# osbo_v10.net
KiCad netlist of a schematic drawn in EAGLE
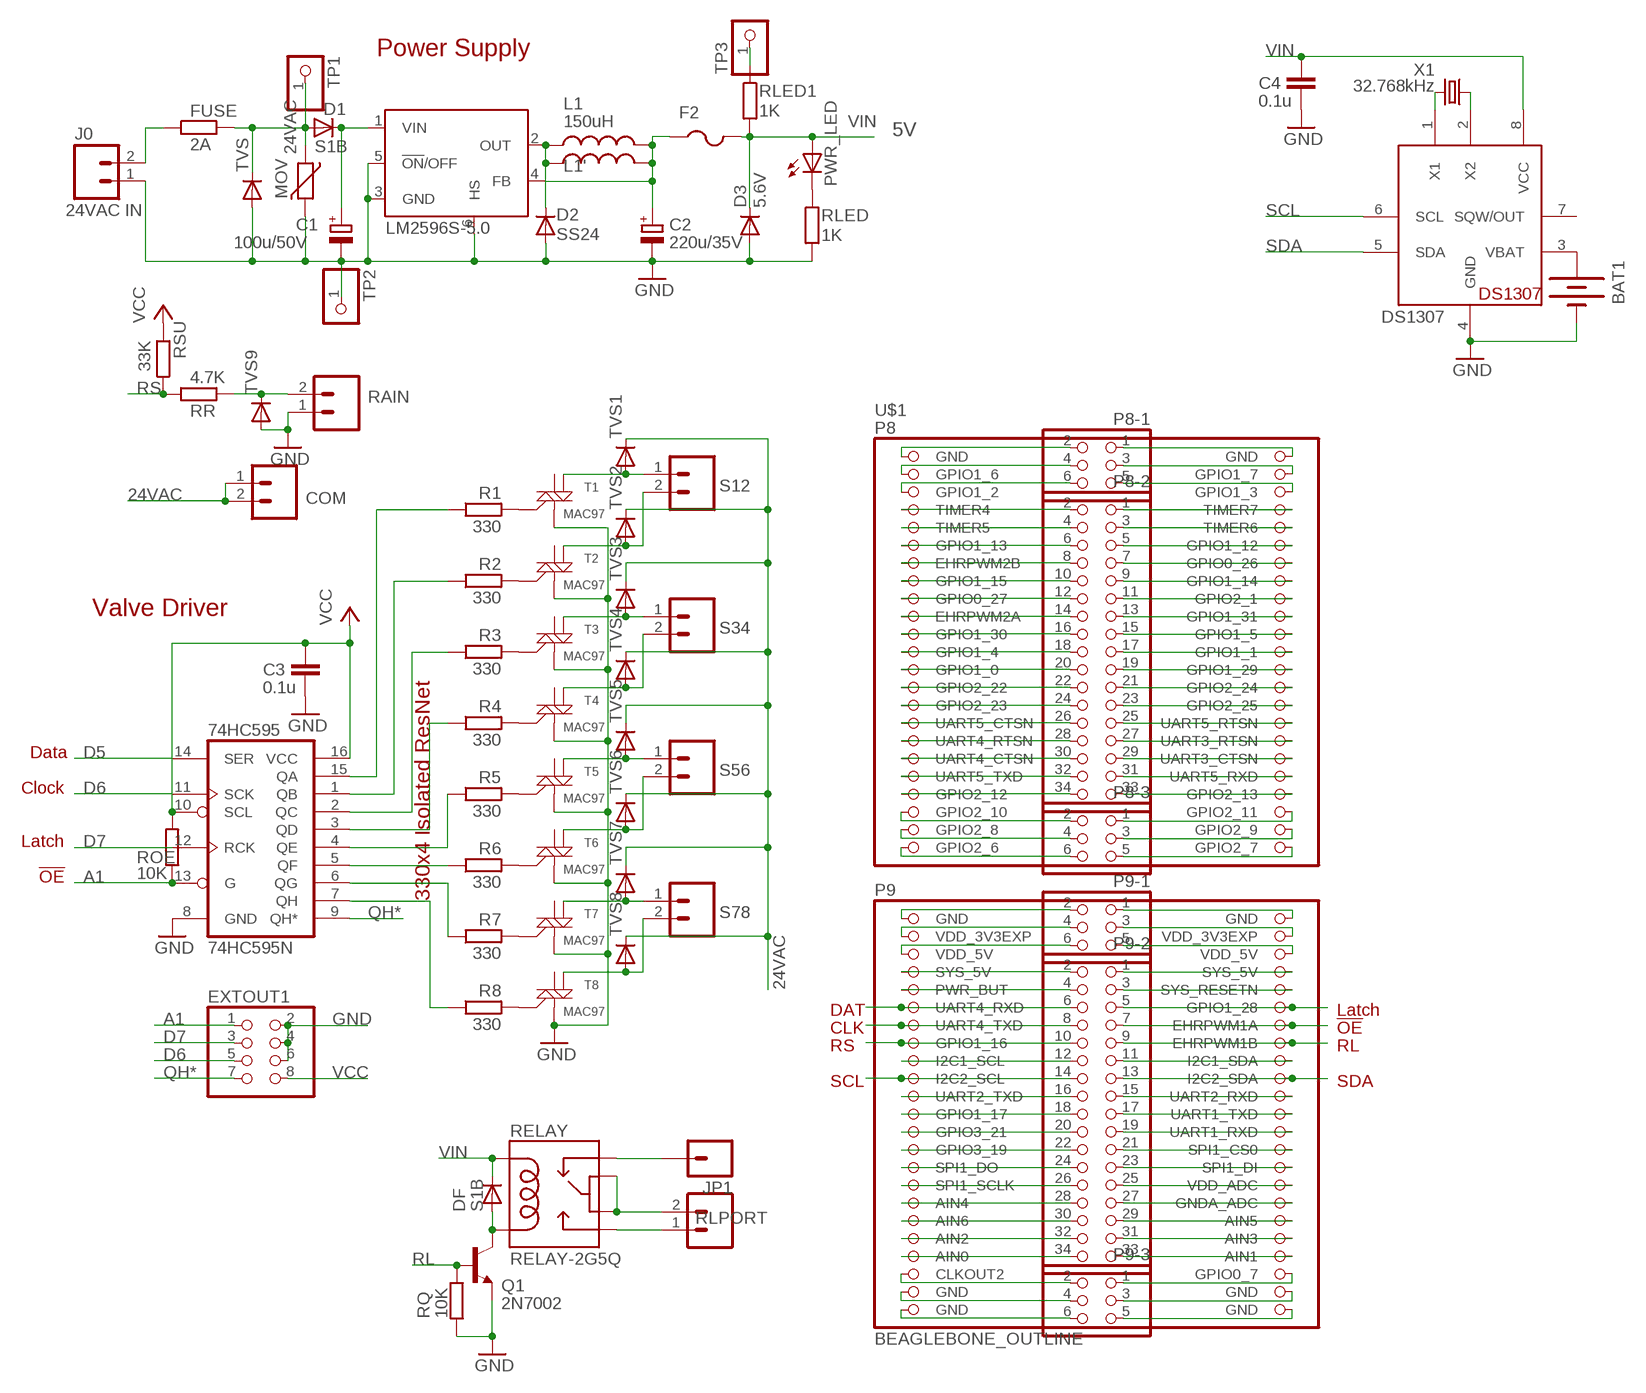
[diagram p0: schematic, sheet 1]

(export (version "E")
  (design (tool "Eeschema 10.0.6"))
  (components
    (comp (ref "74HC595")
      (value "74HC595N")
      (footprint "eagle-import:SO16")
      (libsource (lib "eagle-import") (part "74595DLS"))
    )
    (comp (ref "BAT1")
      (value "BATTERYBATTERY_12MM_SMT")
      (footprint "eagle-import:BATTCON_12MM_SMT")
      (libsource (lib "eagle-import") (part "BATTERYBATTERY_12MM_SMT"))
    )
    (comp (ref "C1")
      (value "100u/50V")
      (footprint "eagle-import:PANASONIC_E")
      (libsource (lib "eagle-import") (part "CPOL-EUE"))
    )
    (comp (ref "C2")
      (value "220u/35V")
      (footprint "eagle-import:PANASONIC_E")
      (libsource (lib "eagle-import") (part "CPOL-EUE"))
    )
    (comp (ref "C3")
      (value "0.1u")
      (footprint "eagle-import:C0805")
      (libsource (lib "eagle-import") (part "C-EUC0805"))
    )
    (comp (ref "C4")
      (value "0.1u")
      (footprint "eagle-import:C0805")
      (libsource (lib "eagle-import") (part "C-EUC0805"))
    )
    (comp (ref "COM")
      (value "M025MM-X")
      (footprint "eagle-import:SCREWTERMINAL-5MM-2-X")
      (libsource (lib "eagle-import") (part "M025MM-X"))
    )
    (comp (ref "D1")
      (value "S1B")
      (footprint "eagle-import:DO-214AC")
      (libsource (lib "eagle-import") (part "DIODE-DO-214AC"))
    )
    (comp (ref "D2")
      (value "SS24")
      (footprint "eagle-import:SMB")
      (libsource (lib "eagle-import") (part "DIODE-SMB"))
    )
    (comp (ref "D3")
      (value "5.6V")
      (footprint "eagle-import:MINIMELF")
      (libsource (lib "eagle-import") (part "DIODE-MINIMELF"))
    )
    (comp (ref "DF")
      (value "S1B")
      (footprint "eagle-import:DO-214AC")
      (libsource (lib "eagle-import") (part "DIODE-DO-214AC"))
    )
    (comp (ref "DS1307")
      (value "DS1307")
      (footprint "eagle-import:SO08")
      (libsource (lib "eagle-import") (part "DS1307SOIC"))
    )
    (comp (ref "EXTOUT1")
      (value "PINHD-2X4/90")
      (footprint "eagle-import:2X04_90")
      (libsource (lib "eagle-import") (part "PINHD-2X4/90"))
    )
    (comp (ref "F2")
      (value "PTCFUSE-1812")
      (footprint "eagle-import:1812")
      (libsource (lib "eagle-import") (part "PTCFUSE-1812"))
    )
    (comp (ref "FUSE")
      (value "2A")
      (footprint "eagle-import:0411_15")
      (libsource (lib "eagle-import") (part "R-EU_0411/15"))
    )
    (comp (ref "IC1")
      (value "LM2596S-5.0")
      (footprint "eagle-import:TO263-5")
      (fields (field (name "MF") "NATIONAL SEMICONDUCTOR") (field (name "MPN") "LM2596S-ADJ/NOPB"))
      (libsource (lib "eagle-import") (part "LM2596S"))
    )
    (comp (ref "J0")
      (value "24VAC IN")
      (footprint "eagle-import:SCREWTERMINAL-4MM-2-X")
      (libsource (lib "eagle-import") (part "M024MM-X"))
    )
    (comp (ref "JP1")
      (value "M01PTH")
      (footprint "eagle-import:1X01")
      (libsource (lib "eagle-import") (part "M01PTH"))
    )
    (comp (ref "L1")
      (value "150uH")
      (footprint "eagle-import:CDRH125")
      (libsource (lib "eagle-import") (part "INDUCTORPWR"))
    )
    (comp (ref "L1'")
      (value "150uH")
      (footprint "eagle-import:0207_7")
      (libsource (lib "eagle-import") (part "L-US0207/7"))
    )
    (comp (ref "MOV")
      (value "VARISTOR-5")
      (footprint "eagle-import:R-5")
      (libsource (lib "eagle-import") (part "VARISTOR-5"))
    )
    (comp (ref "P8-1")
      (value "PINHD-2X3")
      (footprint "eagle-import:2X03")
      (libsource (lib "eagle-import") (part "PINHD-2X3"))
    )
    (comp (ref "P8-2")
      (value "PINHD-2X17")
      (footprint "eagle-import:2X17")
      (libsource (lib "eagle-import") (part "PINHD-2X17"))
    )
    (comp (ref "P8-3")
      (value "PINHD-2X3")
      (footprint "eagle-import:2X03")
      (libsource (lib "eagle-import") (part "PINHD-2X3"))
    )
    (comp (ref "P9-1")
      (value "PINHD-2X3")
      (footprint "eagle-import:2X03")
      (libsource (lib "eagle-import") (part "PINHD-2X3"))
    )
    (comp (ref "P9-2")
      (value "PINHD-2X17")
      (footprint "eagle-import:2X17")
      (libsource (lib "eagle-import") (part "PINHD-2X17"))
    )
    (comp (ref "P9-3")
      (value "PINHD-2X3")
      (footprint "eagle-import:2X03")
      (libsource (lib "eagle-import") (part "PINHD-2X3"))
    )
    (comp (ref "PWR_LED")
      (value "LEDCHIPLED_0805")
      (footprint "eagle-import:CHIPLED_0805")
      (libsource (lib "eagle-import") (part "LEDCHIPLED_0805"))
    )
    (comp (ref "Q1")
      (value "2N7002")
      (footprint "eagle-import:SOT23-3")
      (libsource (lib "eagle-import") (part "TRANSISTOR_NPNSOT23-3"))
    )
    (comp (ref "R1")
      (value "330")
      (footprint "eagle-import:R0805")
      (libsource (lib "eagle-import") (part "R-EU_R0805"))
    )
    (comp (ref "R2")
      (value "330")
      (footprint "eagle-import:R0805")
      (libsource (lib "eagle-import") (part "R-EU_R0805"))
    )
    (comp (ref "R3")
      (value "330")
      (footprint "eagle-import:R0805")
      (libsource (lib "eagle-import") (part "R-EU_R0805"))
    )
    (comp (ref "R4")
      (value "330")
      (footprint "eagle-import:R0805")
      (libsource (lib "eagle-import") (part "R-EU_R0805"))
    )
    (comp (ref "R5")
      (value "330")
      (footprint "eagle-import:R0805")
      (libsource (lib "eagle-import") (part "R-EU_R0805"))
    )
    (comp (ref "R6")
      (value "330")
      (footprint "eagle-import:R0805")
      (libsource (lib "eagle-import") (part "R-EU_R0805"))
    )
    (comp (ref "R7")
      (value "330")
      (footprint "eagle-import:R0805")
      (libsource (lib "eagle-import") (part "R-EU_R0805"))
    )
    (comp (ref "R8")
      (value "330")
      (footprint "eagle-import:R0805")
      (libsource (lib "eagle-import") (part "R-EU_R0805"))
    )
    (comp (ref "RAIN")
      (value "M025MM-X")
      (footprint "eagle-import:SCREWTERMINAL-5MM-2-X")
      (libsource (lib "eagle-import") (part "M025MM-X"))
    )
    (comp (ref "RELAY")
      (value "RELAY-2G5Q")
      (footprint "eagle-import:RELAY-G5V")
      (libsource (lib "eagle-import") (part "RELAY-2G5Q"))
    )
    (comp (ref "RLED")
      (value "1K")
      (footprint "eagle-import:R0805")
      (libsource (lib "eagle-import") (part "R-EU_R0805"))
    )
    (comp (ref "RLED1")
      (value "1K")
      (footprint "eagle-import:R0805")
      (libsource (lib "eagle-import") (part "R-EU_R0805"))
    )
    (comp (ref "RLPORT")
      (value "M025MM")
      (footprint "eagle-import:SCREWTERMINAL-5MM-2")
      (libsource (lib "eagle-import") (part "M025MM"))
    )
    (comp (ref "ROE")
      (value "10K")
      (footprint "eagle-import:R0805")
      (libsource (lib "eagle-import") (part "R-EU_R0805"))
    )
    (comp (ref "RQ")
      (value "10K")
      (footprint "eagle-import:R0805")
      (libsource (lib "eagle-import") (part "R-EU_R0805"))
    )
    (comp (ref "RR")
      (value "4.7K")
      (footprint "eagle-import:R0805")
      (libsource (lib "eagle-import") (part "R-EU_R0805"))
    )
    (comp (ref "RSU")
      (value "33K")
      (footprint "eagle-import:R0805")
      (libsource (lib "eagle-import") (part "R-EU_R0805"))
    )
    (comp (ref "S12")
      (value "M025MM-X")
      (footprint "eagle-import:SCREWTERMINAL-5MM-2-X")
      (libsource (lib "eagle-import") (part "M025MM-X"))
    )
    (comp (ref "S34")
      (value "M025MM-X")
      (footprint "eagle-import:SCREWTERMINAL-5MM-2-X")
      (libsource (lib "eagle-import") (part "M025MM-X"))
    )
    (comp (ref "S56")
      (value "M025MM-X")
      (footprint "eagle-import:SCREWTERMINAL-5MM-2-X")
      (libsource (lib "eagle-import") (part "M025MM-X"))
    )
    (comp (ref "S78")
      (value "M025MM-X")
      (footprint "eagle-import:SCREWTERMINAL-5MM-2-X")
      (libsource (lib "eagle-import") (part "M025MM-X"))
    )
    (comp (ref "T1")
      (value "MAC97")
      (footprint "eagle-import:SOT223")
      (libsource (lib "eagle-import") (part "MAC97SOT223"))
    )
    (comp (ref "T2")
      (value "MAC97")
      (footprint "eagle-import:SOT223")
      (libsource (lib "eagle-import") (part "MAC97SOT223"))
    )
    (comp (ref "T3")
      (value "MAC97")
      (footprint "eagle-import:SOT223")
      (libsource (lib "eagle-import") (part "MAC97SOT223"))
    )
    (comp (ref "T4")
      (value "MAC97")
      (footprint "eagle-import:SOT223")
      (libsource (lib "eagle-import") (part "MAC97SOT223"))
    )
    (comp (ref "T5")
      (value "MAC97")
      (footprint "eagle-import:SOT223")
      (libsource (lib "eagle-import") (part "MAC97SOT223"))
    )
    (comp (ref "T6")
      (value "MAC97")
      (footprint "eagle-import:SOT223")
      (libsource (lib "eagle-import") (part "MAC97SOT223"))
    )
    (comp (ref "T7")
      (value "MAC97")
      (footprint "eagle-import:SOT223")
      (libsource (lib "eagle-import") (part "MAC97SOT223"))
    )
    (comp (ref "T8")
      (value "MAC97")
      (footprint "eagle-import:SOT223")
      (libsource (lib "eagle-import") (part "MAC97SOT223"))
    )
    (comp (ref "TP1")
      (value "PINHD-1X1CB")
      (footprint "eagle-import:1X01-CLEANBIG")
      (libsource (lib "eagle-import") (part "PINHD-1X1CB"))
    )
    (comp (ref "TP2")
      (value "PINHD-1X1CB")
      (footprint "eagle-import:1X01-CLEANBIG")
      (libsource (lib "eagle-import") (part "PINHD-1X1CB"))
    )
    (comp (ref "TP3")
      (value "PINHD-1X1CB")
      (footprint "eagle-import:1X01-CLEANBIG")
      (libsource (lib "eagle-import") (part "PINHD-1X1CB"))
    )
    (comp (ref "TVS")
      (value "DIODE-SMB")
      (footprint "eagle-import:SMB")
      (libsource (lib "eagle-import") (part "DIODE-SMB"))
    )
    (comp (ref "TVS1")
      (value "DIODE-SMB")
      (footprint "eagle-import:SMB")
      (libsource (lib "eagle-import") (part "DIODE-SMB"))
    )
    (comp (ref "TVS2")
      (value "DIODE-SMB")
      (footprint "eagle-import:SMB")
      (libsource (lib "eagle-import") (part "DIODE-SMB"))
    )
    (comp (ref "TVS3")
      (value "DIODE-SMB")
      (footprint "eagle-import:SMB")
      (libsource (lib "eagle-import") (part "DIODE-SMB"))
    )
    (comp (ref "TVS4")
      (value "DIODE-SMB")
      (footprint "eagle-import:SMB")
      (libsource (lib "eagle-import") (part "DIODE-SMB"))
    )
    (comp (ref "TVS5")
      (value "DIODE-SMB")
      (footprint "eagle-import:SMB")
      (libsource (lib "eagle-import") (part "DIODE-SMB"))
    )
    (comp (ref "TVS6")
      (value "DIODE-SMB")
      (footprint "eagle-import:SMB")
      (libsource (lib "eagle-import") (part "DIODE-SMB"))
    )
    (comp (ref "TVS7")
      (value "DIODE-SMB")
      (footprint "eagle-import:SMB")
      (libsource (lib "eagle-import") (part "DIODE-SMB"))
    )
    (comp (ref "TVS8")
      (value "DIODE-SMB")
      (footprint "eagle-import:SMB")
      (libsource (lib "eagle-import") (part "DIODE-SMB"))
    )
    (comp (ref "TVS9")
      (value "DIODE-SMB")
      (footprint "eagle-import:SMB")
      (libsource (lib "eagle-import") (part "DIODE-SMB"))
    )
    (comp (ref "U$1")
      (value "BEAGLEBONE_OUTLINE")
      (footprint "eagle-import:BEAGLEBONE_SHIELD")
      (libsource (lib "eagle-import") (part "BEAGLEBONE_OUTLINE"))
    )
    (comp (ref "X1")
      (value "32.768kHz")
      (footprint "eagle-import:MM20SS")
      (libsource (lib "eagle-import") (part "CRYSTALMM20SS"))
    )
  )
  (nets
    (net (code "1") (name "/24VAC") (class "Default")
      (node (ref "COM") (pin "1") (pinfunction "1_1") (pintype "passive"))
      (node (ref "COM") (pin "2") (pinfunction "2_2") (pintype "passive"))
      (node (ref "D1") (pin "A") (pinfunction "A_A") (pintype "passive"))
      (node (ref "FUSE") (pin "2") (pinfunction "2_2") (pintype "passive"))
      (node (ref "MOV") (pin "1") (pinfunction "1_1") (pintype "passive"))
      (node (ref "TP1") (pin "1") (pinfunction "1_1") (pintype "passive"))
      (node (ref "TVS") (pin "C") (pinfunction "C_C") (pintype "passive"))
      (node (ref "TVS1") (pin "C") (pinfunction "C_C") (pintype "passive"))
      (node (ref "TVS2") (pin "C") (pinfunction "C_C") (pintype "passive"))
      (node (ref "TVS3") (pin "C") (pinfunction "C_C") (pintype "passive"))
      (node (ref "TVS4") (pin "C") (pinfunction "C_C") (pintype "passive"))
      (node (ref "TVS5") (pin "C") (pinfunction "C_C") (pintype "passive"))
      (node (ref "TVS6") (pin "C") (pinfunction "C_C") (pintype "passive"))
      (node (ref "TVS7") (pin "C") (pinfunction "C_C") (pintype "passive"))
      (node (ref "TVS8") (pin "C") (pinfunction "C_C") (pintype "passive"))
    )
    (net (code "2") (name "/A1") (class "Default")
      (node (ref "74HC595") (pin "13") (pinfunction "G_13") (pintype "input"))
      (node (ref "EXTOUT1") (pin "1") (pinfunction "1_1") (pintype "passive"))
      (node (ref "P9-2") (pin "7") (pinfunction "7_7") (pintype "passive"))
      (node (ref "ROE") (pin "1") (pinfunction "1_1") (pintype "passive"))
      (node (ref "U$1") (pin "60") (pinfunction "EHRPWM1A_60") (pintype "passive"))
    )
    (net (code "3") (name "/D5") (class "Default")
      (node (ref "74HC595") (pin "14") (pinfunction "SER_14") (pintype "input"))
      (node (ref "P9-2") (pin "6") (pinfunction "6_6") (pintype "passive"))
      (node (ref "U$1") (pin "57") (pinfunction "UART4_RXD_57") (pintype "passive"))
    )
    (net (code "4") (name "/D6") (class "Default")
      (node (ref "74HC595") (pin "11") (pinfunction "SCK_11") (pintype "input"))
      (node (ref "EXTOUT1") (pin "5") (pinfunction "5_5") (pintype "passive"))
      (node (ref "P9-2") (pin "8") (pinfunction "8_8") (pintype "passive"))
      (node (ref "U$1") (pin "59") (pinfunction "UART4_TXD_59") (pintype "passive"))
    )
    (net (code "5") (name "/D7") (class "Default")
      (node (ref "74HC595") (pin "12") (pinfunction "RCK_12") (pintype "input"))
      (node (ref "EXTOUT1") (pin "3") (pinfunction "3_3") (pintype "passive"))
      (node (ref "P9-2") (pin "5") (pinfunction "5_5") (pintype "passive"))
      (node (ref "U$1") (pin "58") (pinfunction "GPIO1_28_58") (pintype "passive"))
    )
    (net (code "6") (name "/QH*") (class "Default")
      (node (ref "74HC595") (pin "9") (pinfunction "QH*_9") (pintype "tri_state"))
      (node (ref "EXTOUT1") (pin "7") (pinfunction "7_7") (pintype "passive"))
    )
    (net (code "7") (name "/RL") (class "Default")
      (node (ref "P9-2") (pin "9") (pinfunction "9_9") (pintype "passive"))
      (node (ref "Q1") (pin "1") (pinfunction "B_1") (pintype "passive"))
      (node (ref "RQ") (pin "1") (pinfunction "1_1") (pintype "passive"))
      (node (ref "U$1") (pin "62") (pinfunction "EHRPWM1B_62") (pintype "passive"))
    )
    (net (code "8") (name "/RS") (class "Default")
      (node (ref "P9-2") (pin "10") (pinfunction "10_10") (pintype "passive"))
      (node (ref "RR") (pin "2") (pinfunction "2_2") (pintype "passive"))
      (node (ref "RSU") (pin "1") (pinfunction "1_1") (pintype "passive"))
      (node (ref "U$1") (pin "61") (pinfunction "GPIO1_16_61") (pintype "passive"))
    )
    (net (code "9") (name "/SCL") (class "Default")
      (node (ref "DS1307") (pin "6") (pinfunction "SCL_6") (pintype "bidirectional"))
      (node (ref "P9-2") (pin "14") (pinfunction "14_14") (pintype "passive"))
      (node (ref "U$1") (pin "65") (pinfunction "I2C2_SCL_65") (pintype "passive"))
    )
    (net (code "10") (name "/SDA") (class "Default")
      (node (ref "DS1307") (pin "5") (pinfunction "SDA_5") (pintype "bidirectional"))
      (node (ref "P9-2") (pin "13") (pinfunction "13_13") (pintype "passive"))
      (node (ref "U$1") (pin "66") (pinfunction "I2C2_SDA_66") (pintype "passive"))
    )
    (net (code "11") (name "/SYS_5V") (class "Default")
      (node (ref "P9-2") (pin "1") (pinfunction "1_1") (pintype "passive"))
      (node (ref "P9-2") (pin "2") (pinfunction "2_2") (pintype "passive"))
      (node (ref "U$1") (pin "53") (pinfunction "SYS_5V_53") (pintype "power_in"))
      (node (ref "U$1") (pin "54") (pinfunction "SYS_5V_54") (pintype "passive"))
    )
    (net (code "12") (name "/VIN") (class "Default")
      (node (ref "C4") (pin "1") (pinfunction "1_1") (pintype "passive"))
      (node (ref "D3") (pin "C") (pinfunction "C_C") (pintype "passive"))
      (node (ref "DF") (pin "C") (pinfunction "C_C") (pintype "passive"))
      (node (ref "DS1307") (pin "8") (pinfunction "VCC_8") (pintype "power_in"))
      (node (ref "F2") (pin "2") (pinfunction "2_2") (pintype "passive"))
      (node (ref "P9-1") (pin "5") (pinfunction "5_5") (pintype "passive"))
      (node (ref "P9-1") (pin "6") (pinfunction "6_6") (pintype "passive"))
      (node (ref "PWR_LED") (pin "A") (pinfunction "A_A") (pintype "passive"))
      (node (ref "RELAY") (pin "2") (pinfunction "2_2") (pintype "bidirectional"))
      (node (ref "RLED1") (pin "2") (pinfunction "2_2") (pintype "passive"))
      (node (ref "U$1") (pin "51") (pinfunction "VDD_5V_51") (pintype "power_in"))
      (node (ref "U$1") (pin "52") (pinfunction "VDD_5V_52") (pintype "power_in"))
    )
    (net (code "13") (name "GND") (class "Default")
      (node (ref "74HC595") (pin "8") (pinfunction "GND_8") (pintype "power_in"))
      (node (ref "BAT1") (pin "P$1") (pinfunction "-_P$1") (pintype "power_in"))
      (node (ref "C1") (pin "-") (pinfunction "-_-") (pintype "passive"))
      (node (ref "C2") (pin "-") (pinfunction "-_-") (pintype "passive"))
      (node (ref "C3") (pin "2") (pinfunction "2_2") (pintype "passive"))
      (node (ref "C4") (pin "2") (pinfunction "2_2") (pintype "passive"))
      (node (ref "D2") (pin "A") (pinfunction "A_A") (pintype "passive"))
      (node (ref "D3") (pin "A") (pinfunction "A_A") (pintype "passive"))
      (node (ref "DS1307") (pin "4") (pinfunction "GND_4") (pintype "power_in"))
      (node (ref "EXTOUT1") (pin "2") (pinfunction "2_2") (pintype "passive"))
      (node (ref "EXTOUT1") (pin "4") (pinfunction "4_4") (pintype "passive"))
      (node (ref "EXTOUT1") (pin "6") (pinfunction "6_6") (pintype "passive"))
      (node (ref "IC1") (pin "3") (pinfunction "GND_3") (pintype "power_in"))
      (node (ref "IC1") (pin "5") (pinfunction "~{ON}/OFF_5") (pintype "input"))
      (node (ref "IC1") (pin "6") (pinfunction "HS_6") (pintype "power_in"))
      (node (ref "J0") (pin "1") (pinfunction "1_1") (pintype "passive"))
      (node (ref "MOV") (pin "2") (pinfunction "2_2") (pintype "passive"))
      (node (ref "P9-1") (pin "1") (pinfunction "1_1") (pintype "passive"))
      (node (ref "P9-1") (pin "2") (pinfunction "2_2") (pintype "passive"))
      (node (ref "Q1") (pin "2") (pinfunction "E_2") (pintype "passive"))
      (node (ref "RAIN") (pin "1") (pinfunction "1_1") (pintype "passive"))
      (node (ref "RLED") (pin "2") (pinfunction "2_2") (pintype "passive"))
      (node (ref "RQ") (pin "2") (pinfunction "2_2") (pintype "passive"))
      (node (ref "T1") (pin "1") (pinfunction "M1_1") (pintype "bidirectional"))
      (node (ref "T2") (pin "1") (pinfunction "M1_1") (pintype "bidirectional"))
      (node (ref "T3") (pin "1") (pinfunction "M1_1") (pintype "bidirectional"))
      (node (ref "T4") (pin "1") (pinfunction "M1_1") (pintype "bidirectional"))
      (node (ref "T5") (pin "1") (pinfunction "M1_1") (pintype "bidirectional"))
      (node (ref "T6") (pin "1") (pinfunction "M1_1") (pintype "bidirectional"))
      (node (ref "T7") (pin "1") (pinfunction "M1_1") (pintype "bidirectional"))
      (node (ref "T8") (pin "1") (pinfunction "M1_1") (pintype "bidirectional"))
      (node (ref "TP2") (pin "1") (pinfunction "1_1") (pintype "passive"))
      (node (ref "TVS") (pin "A") (pinfunction "A_A") (pintype "passive"))
      (node (ref "TVS9") (pin "A") (pinfunction "A_A") (pintype "passive"))
      (node (ref "U$1") (pin "47") (pinfunction "GND_47") (pintype "power_in"))
      (node (ref "U$1") (pin "48") (pinfunction "GND_48") (pintype "power_in"))
    )
    (net (code "14") (name "Net-(74HC595-QA)") (class "Default")
      (node (ref "74HC595") (pin "15") (pinfunction "QA_15") (pintype "tri_state"))
      (node (ref "R1") (pin "1") (pinfunction "1_1") (pintype "passive"))
    )
    (net (code "15") (name "Net-(74HC595-QB)") (class "Default")
      (node (ref "74HC595") (pin "1") (pinfunction "QB_1") (pintype "tri_state"))
      (node (ref "R2") (pin "1") (pinfunction "1_1") (pintype "passive"))
    )
    (net (code "16") (name "Net-(74HC595-QC)") (class "Default")
      (node (ref "74HC595") (pin "2") (pinfunction "QC_2") (pintype "tri_state"))
      (node (ref "R3") (pin "1") (pinfunction "1_1") (pintype "passive"))
    )
    (net (code "17") (name "Net-(74HC595-QD)") (class "Default")
      (node (ref "74HC595") (pin "3") (pinfunction "QD_3") (pintype "tri_state"))
      (node (ref "R4") (pin "1") (pinfunction "1_1") (pintype "passive"))
    )
    (net (code "18") (name "Net-(74HC595-QE)") (class "Default")
      (node (ref "74HC595") (pin "4") (pinfunction "QE_4") (pintype "tri_state"))
      (node (ref "R5") (pin "1") (pinfunction "1_1") (pintype "passive"))
    )
    (net (code "19") (name "Net-(74HC595-QF)") (class "Default")
      (node (ref "74HC595") (pin "5") (pinfunction "QF_5") (pintype "tri_state"))
      (node (ref "R6") (pin "1") (pinfunction "1_1") (pintype "passive"))
    )
    (net (code "20") (name "Net-(74HC595-QG)") (class "Default")
      (node (ref "74HC595") (pin "6") (pinfunction "QG_6") (pintype "tri_state"))
      (node (ref "R7") (pin "1") (pinfunction "1_1") (pintype "passive"))
    )
    (net (code "21") (name "Net-(74HC595-QH)") (class "Default")
      (node (ref "74HC595") (pin "7") (pinfunction "QH_7") (pintype "tri_state"))
      (node (ref "R8") (pin "1") (pinfunction "1_1") (pintype "passive"))
    )
    (net (code "22") (name "Net-(BAT1-+)") (class "Default")
      (node (ref "BAT1") (pin "P$2") (pinfunction "+_P$2") (pintype "power_in"))
      (node (ref "DS1307") (pin "3") (pinfunction "VBAT_3") (pintype "power_in"))
    )
    (net (code "23") (name "Net-(DS1307-X1)") (class "Default")
      (node (ref "DS1307") (pin "1") (pinfunction "X1_1") (pintype "passive"))
      (node (ref "X1") (pin "1") (pinfunction "1_1") (pintype "passive"))
    )
    (net (code "24") (name "Net-(DS1307-X2)") (class "Default")
      (node (ref "DS1307") (pin "2") (pinfunction "X2_2") (pintype "passive"))
      (node (ref "X1") (pin "4") (pinfunction "2_4") (pintype "passive"))
    )
    (net (code "25") (name "Net-(FUSE-Pad1)") (class "Default")
      (node (ref "FUSE") (pin "1") (pinfunction "1_1") (pintype "passive"))
      (node (ref "J0") (pin "2") (pinfunction "2_2") (pintype "passive"))
    )
    (net (code "26") (name "Net-(IC1-FB)") (class "Default")
      (node (ref "C2") (pin "+") (pinfunction "+_+") (pintype "passive"))
      (node (ref "F2") (pin "1") (pinfunction "1_1") (pintype "passive"))
      (node (ref "IC1") (pin "4") (pinfunction "FB_4") (pintype "input"))
      (node (ref "L1") (pin "2") (pinfunction "2_2") (pintype "passive"))
      (node (ref "L1'") (pin "2") (pinfunction "2_2") (pintype "passive"))
    )
    (net (code "27") (name "Net-(IC1-OUT)") (class "Default")
      (node (ref "D2") (pin "C") (pinfunction "C_C") (pintype "passive"))
      (node (ref "IC1") (pin "2") (pinfunction "OUT_2") (pintype "output"))
      (node (ref "L1") (pin "1") (pinfunction "1_1") (pintype "passive"))
      (node (ref "L1'") (pin "1") (pinfunction "1_1") (pintype "passive"))
    )
    (net (code "28") (name "Net-(IC1-VIN)") (class "Default")
      (node (ref "C1") (pin "+") (pinfunction "+_+") (pintype "passive"))
      (node (ref "D1") (pin "C") (pinfunction "C_C") (pintype "passive"))
      (node (ref "IC1") (pin "1") (pinfunction "VIN_1") (pintype "input"))
    )
    (net (code "29") (name "Net-(JP1-Pad1)") (class "Default")
      (node (ref "JP1") (pin "1") (pinfunction "1_1") (pintype "passive"))
      (node (ref "RELAY") (pin "1") (pinfunction "1_1") (pintype "bidirectional"))
    )
    (net (code "30") (name "Net-(P8-1-Pad1)") (class "Default")
      (node (ref "P8-1") (pin "1") (pinfunction "1_1") (pintype "passive"))
      (node (ref "U$1") (pin "2") (pinfunction "GND_2") (pintype "power_in"))
    )
    (net (code "31") (name "Net-(P8-1-Pad2)") (class "Default")
      (node (ref "P8-1") (pin "2") (pinfunction "2_2") (pintype "passive"))
      (node (ref "U$1") (pin "1") (pinfunction "GND_1") (pintype "power_in"))
    )
    (net (code "32") (name "Net-(P9-3-Pad3)") (class "Default")
      (node (ref "P9-3") (pin "3") (pinfunction "3_3") (pintype "passive"))
      (node (ref "U$1") (pin "90") (pinfunction "GND_90") (pintype "power_in"))
    )
    (net (code "33") (name "Net-(P9-3-Pad4)") (class "Default")
      (node (ref "P9-3") (pin "4") (pinfunction "4_4") (pintype "passive"))
      (node (ref "U$1") (pin "89") (pinfunction "GND_89") (pintype "power_in"))
    )
    (net (code "34") (name "Net-(P9-3-Pad5)") (class "Default")
      (node (ref "P9-3") (pin "5") (pinfunction "5_5") (pintype "passive"))
      (node (ref "U$1") (pin "92") (pinfunction "GND_92") (pintype "power_in"))
    )
    (net (code "35") (name "Net-(P9-3-Pad6)") (class "Default")
      (node (ref "P9-3") (pin "6") (pinfunction "6_6") (pintype "passive"))
      (node (ref "U$1") (pin "91") (pinfunction "GND_91") (pintype "power_in"))
    )
    (net (code "36") (name "Net-(PWR_LED-PadC)") (class "Default")
      (node (ref "PWR_LED") (pin "C") (pinfunction "C_C") (pintype "passive"))
      (node (ref "RLED") (pin "1") (pinfunction "1_1") (pintype "passive"))
    )
    (net (code "37") (name "Net-(Q1-C)") (class "Default")
      (node (ref "DF") (pin "A") (pinfunction "A_A") (pintype "passive"))
      (node (ref "Q1") (pin "3") (pinfunction "C_3") (pintype "passive"))
      (node (ref "RELAY") (pin "9") (pinfunction "9_9") (pintype "bidirectional"))
    )
    (net (code "38") (name "Net-(RAIN-Pad2)") (class "Default")
      (node (ref "RAIN") (pin "2") (pinfunction "2_2") (pintype "passive"))
      (node (ref "RR") (pin "1") (pinfunction "1_1") (pintype "passive"))
      (node (ref "TVS9") (pin "C") (pinfunction "C_C") (pintype "passive"))
    )
    (net (code "39") (name "Net-(RELAY-Pad5)") (class "Default")
      (node (ref "RELAY") (pin "5") (pinfunction "5_5") (pintype "bidirectional"))
      (node (ref "RELAY") (pin "6") (pinfunction "6_6") (pintype "bidirectional"))
      (node (ref "RLPORT") (pin "2") (pinfunction "2_2") (pintype "passive"))
    )
    (net (code "40") (name "Net-(RELAY-Pad10)") (class "Default")
      (node (ref "RELAY") (pin "10") (pinfunction "10_10") (pintype "bidirectional"))
      (node (ref "RLPORT") (pin "1") (pinfunction "1_1") (pintype "passive"))
    )
    (net (code "41") (name "Net-(RLED1-Pad1)") (class "Default")
      (node (ref "RLED1") (pin "1") (pinfunction "1_1") (pintype "passive"))
      (node (ref "TP3") (pin "1") (pinfunction "1_1") (pintype "passive"))
    )
    (net (code "42") (name "Net-(T1-G)") (class "Default")
      (node (ref "R1") (pin "2") (pinfunction "2_2") (pintype "passive"))
      (node (ref "T1") (pin "3") (pinfunction "G_3") (pintype "bidirectional"))
    )
    (net (code "43") (name "Net-(T1-M2-4)") (class "Default")
      (node (ref "S12") (pin "1") (pinfunction "1_1") (pintype "passive"))
      (node (ref "T1") (pin "4") (pinfunction "M2-4_4") (pintype "bidirectional"))
      (node (ref "TVS1") (pin "A") (pinfunction "A_A") (pintype "passive"))
    )
    (net (code "44") (name "Net-(T2-G)") (class "Default")
      (node (ref "R2") (pin "2") (pinfunction "2_2") (pintype "passive"))
      (node (ref "T2") (pin "3") (pinfunction "G_3") (pintype "bidirectional"))
    )
    (net (code "45") (name "Net-(T2-M2-4)") (class "Default")
      (node (ref "S12") (pin "2") (pinfunction "2_2") (pintype "passive"))
      (node (ref "T2") (pin "4") (pinfunction "M2-4_4") (pintype "bidirectional"))
      (node (ref "TVS2") (pin "A") (pinfunction "A_A") (pintype "passive"))
    )
    (net (code "46") (name "Net-(T3-G)") (class "Default")
      (node (ref "R3") (pin "2") (pinfunction "2_2") (pintype "passive"))
      (node (ref "T3") (pin "3") (pinfunction "G_3") (pintype "bidirectional"))
    )
    (net (code "47") (name "Net-(T3-M2-4)") (class "Default")
      (node (ref "S34") (pin "1") (pinfunction "1_1") (pintype "passive"))
      (node (ref "T3") (pin "4") (pinfunction "M2-4_4") (pintype "bidirectional"))
      (node (ref "TVS3") (pin "A") (pinfunction "A_A") (pintype "passive"))
    )
    (net (code "48") (name "Net-(T4-G)") (class "Default")
      (node (ref "R4") (pin "2") (pinfunction "2_2") (pintype "passive"))
      (node (ref "T4") (pin "3") (pinfunction "G_3") (pintype "bidirectional"))
    )
    (net (code "49") (name "Net-(T4-M2-4)") (class "Default")
      (node (ref "S34") (pin "2") (pinfunction "2_2") (pintype "passive"))
      (node (ref "T4") (pin "4") (pinfunction "M2-4_4") (pintype "bidirectional"))
      (node (ref "TVS4") (pin "A") (pinfunction "A_A") (pintype "passive"))
    )
    (net (code "50") (name "Net-(T5-G)") (class "Default")
      (node (ref "R5") (pin "2") (pinfunction "2_2") (pintype "passive"))
      (node (ref "T5") (pin "3") (pinfunction "G_3") (pintype "bidirectional"))
    )
    (net (code "51") (name "Net-(T5-M2-4)") (class "Default")
      (node (ref "S56") (pin "1") (pinfunction "1_1") (pintype "passive"))
      (node (ref "T5") (pin "4") (pinfunction "M2-4_4") (pintype "bidirectional"))
      (node (ref "TVS5") (pin "A") (pinfunction "A_A") (pintype "passive"))
    )
    (net (code "52") (name "Net-(T6-G)") (class "Default")
      (node (ref "R6") (pin "2") (pinfunction "2_2") (pintype "passive"))
      (node (ref "T6") (pin "3") (pinfunction "G_3") (pintype "bidirectional"))
    )
    (net (code "53") (name "Net-(T6-M2-4)") (class "Default")
      (node (ref "S56") (pin "2") (pinfunction "2_2") (pintype "passive"))
      (node (ref "T6") (pin "4") (pinfunction "M2-4_4") (pintype "bidirectional"))
      (node (ref "TVS6") (pin "A") (pinfunction "A_A") (pintype "passive"))
    )
    (net (code "54") (name "Net-(T7-G)") (class "Default")
      (node (ref "R7") (pin "2") (pinfunction "2_2") (pintype "passive"))
      (node (ref "T7") (pin "3") (pinfunction "G_3") (pintype "bidirectional"))
    )
    (net (code "55") (name "Net-(T7-M2-4)") (class "Default")
      (node (ref "S78") (pin "1") (pinfunction "1_1") (pintype "passive"))
      (node (ref "T7") (pin "4") (pinfunction "M2-4_4") (pintype "bidirectional"))
      (node (ref "TVS7") (pin "A") (pinfunction "A_A") (pintype "passive"))
    )
    (net (code "56") (name "Net-(T8-G)") (class "Default")
      (node (ref "R8") (pin "2") (pinfunction "2_2") (pintype "passive"))
      (node (ref "T8") (pin "3") (pinfunction "G_3") (pintype "bidirectional"))
    )
    (net (code "57") (name "Net-(T8-M2-4)") (class "Default")
      (node (ref "S78") (pin "2") (pinfunction "2_2") (pintype "passive"))
      (node (ref "T8") (pin "4") (pinfunction "M2-4_4") (pintype "bidirectional"))
      (node (ref "TVS8") (pin "A") (pinfunction "A_A") (pintype "passive"))
    )
    (net (code "58") (name "Net-(U$1-AIN0)") (class "Default")
      (node (ref "P9-2") (pin "34") (pinfunction "34_34") (pintype "passive"))
      (node (ref "U$1") (pin "85") (pinfunction "AIN0_85") (pintype "power_in"))
    )
    (net (code "59") (name "Net-(U$1-AIN1)") (class "Default")
      (node (ref "P9-2") (pin "33") (pinfunction "33_33") (pintype "passive"))
      (node (ref "U$1") (pin "86") (pinfunction "AIN1_86") (pintype "passive"))
    )
    (net (code "60") (name "Net-(U$1-AIN2)") (class "Default")
      (node (ref "P9-2") (pin "32") (pinfunction "32_32") (pintype "passive"))
      (node (ref "U$1") (pin "83") (pinfunction "AIN2_83") (pintype "passive"))
    )
    (net (code "61") (name "Net-(U$1-AIN3)") (class "Default")
      (node (ref "P9-2") (pin "31") (pinfunction "31_31") (pintype "passive"))
      (node (ref "U$1") (pin "84") (pinfunction "AIN3_84") (pintype "passive"))
    )
    (net (code "62") (name "Net-(U$1-AIN4)") (class "Default")
      (node (ref "P9-2") (pin "28") (pinfunction "28_28") (pintype "passive"))
      (node (ref "U$1") (pin "79") (pinfunction "AIN4_79") (pintype "passive"))
    )
    (net (code "63") (name "Net-(U$1-AIN5)") (class "Default")
      (node (ref "P9-2") (pin "29") (pinfunction "29_29") (pintype "passive"))
      (node (ref "U$1") (pin "82") (pinfunction "AIN5_82") (pintype "passive"))
    )
    (net (code "64") (name "Net-(U$1-AIN6)") (class "Default")
      (node (ref "P9-2") (pin "30") (pinfunction "30_30") (pintype "passive"))
      (node (ref "U$1") (pin "81") (pinfunction "AIN6_81") (pintype "passive"))
    )
    (net (code "65") (name "Net-(U$1-CLKOUT2)") (class "Default")
      (node (ref "P9-3") (pin "2") (pinfunction "2_2") (pintype "passive"))
      (node (ref "U$1") (pin "87") (pinfunction "CLKOUT2_87") (pintype "input"))
    )
    (net (code "66") (name "Net-(U$1-EHRPWM2A)") (class "Default")
      (node (ref "P8-2") (pin "14") (pinfunction "14_14") (pintype "passive"))
      (node (ref "U$1") (pin "19") (pinfunction "EHRPWM2A_19") (pintype "passive"))
    )
    (net (code "67") (name "Net-(U$1-EHRPWM2B)") (class "Default")
      (node (ref "P8-2") (pin "8") (pinfunction "8_8") (pintype "passive"))
      (node (ref "U$1") (pin "13") (pinfunction "EHRPWM2B_13") (pintype "passive"))
    )
    (net (code "68") (name "Net-(U$1-GNDA_ADC)") (class "Default")
      (node (ref "P9-2") (pin "27") (pinfunction "27_27") (pintype "passive"))
      (node (ref "U$1") (pin "80") (pinfunction "GNDA_ADC_80") (pintype "passive"))
    )
    (net (code "69") (name "Net-(U$1-GPIO0_7)") (class "Default")
      (node (ref "P9-3") (pin "1") (pinfunction "1_1") (pintype "passive"))
      (node (ref "U$1") (pin "88") (pinfunction "GPIO0_7_88") (pintype "passive"))
    )
    (net (code "70") (name "Net-(U$1-GPIO0_26)") (class "Default")
      (node (ref "P8-2") (pin "7") (pinfunction "7_7") (pintype "passive"))
      (node (ref "U$1") (pin "14") (pinfunction "GPIO0_26_14") (pintype "passive"))
    )
    (net (code "71") (name "Net-(U$1-GPIO0_27)") (class "Default")
      (node (ref "P8-2") (pin "12") (pinfunction "12_12") (pintype "passive"))
      (node (ref "U$1") (pin "17") (pinfunction "GPIO0_27_17") (pintype "passive"))
    )
    (net (code "72") (name "Net-(U$1-GPIO1_0)") (class "Default")
      (node (ref "P8-2") (pin "20") (pinfunction "20_20") (pintype "passive"))
      (node (ref "U$1") (pin "25") (pinfunction "GPIO1_0_25") (pintype "passive"))
    )
    (net (code "73") (name "Net-(U$1-GPIO1_1)") (class "Default")
      (node (ref "P8-2") (pin "17") (pinfunction "17_17") (pintype "passive"))
      (node (ref "U$1") (pin "24") (pinfunction "GPIO1_1_24") (pintype "passive"))
    )
    (net (code "74") (name "Net-(U$1-GPIO1_2)") (class "Default")
      (node (ref "P8-1") (pin "6") (pinfunction "6_6") (pintype "passive"))
      (node (ref "U$1") (pin "5") (pinfunction "GPIO1_2_5") (pintype "passive"))
    )
    (net (code "75") (name "Net-(U$1-GPIO1_3)") (class "Default")
      (node (ref "P8-1") (pin "5") (pinfunction "5_5") (pintype "passive"))
      (node (ref "U$1") (pin "6") (pinfunction "GPIO1_3_6") (pintype "passive"))
    )
    (net (code "76") (name "Net-(U$1-GPIO1_4)") (class "Default")
      (node (ref "P8-2") (pin "18") (pinfunction "18_18") (pintype "passive"))
      (node (ref "U$1") (pin "23") (pinfunction "GPIO1_4_23") (pintype "passive"))
    )
    (net (code "77") (name "Net-(U$1-GPIO1_5)") (class "Default")
      (node (ref "P8-2") (pin "15") (pinfunction "15_15") (pintype "passive"))
      (node (ref "U$1") (pin "22") (pinfunction "GPIO1_5_22") (pintype "passive"))
    )
    (net (code "78") (name "Net-(U$1-GPIO1_6)") (class "Default")
      (node (ref "P8-1") (pin "4") (pinfunction "4_4") (pintype "passive"))
      (node (ref "U$1") (pin "3") (pinfunction "GPIO1_6_3") (pintype "passive"))
    )
    (net (code "79") (name "Net-(U$1-GPIO1_7)") (class "Default")
      (node (ref "P8-1") (pin "3") (pinfunction "3_3") (pintype "passive"))
      (node (ref "U$1") (pin "4") (pinfunction "GPIO1_7_4") (pintype "passive"))
    )
    (net (code "80") (name "Net-(U$1-GPIO1_12)") (class "Default")
      (node (ref "P8-2") (pin "5") (pinfunction "5_5") (pintype "passive"))
      (node (ref "U$1") (pin "12") (pinfunction "GPIO1_12_12") (pintype "passive"))
    )
    (net (code "81") (name "Net-(U$1-GPIO1_13)") (class "Default")
      (node (ref "P8-2") (pin "6") (pinfunction "6_6") (pintype "passive"))
      (node (ref "U$1") (pin "11") (pinfunction "GPIO1_13_11") (pintype "passive"))
    )
    (net (code "82") (name "Net-(U$1-GPIO1_14)") (class "Default")
      (node (ref "P8-2") (pin "9") (pinfunction "9_9") (pintype "passive"))
      (node (ref "U$1") (pin "16") (pinfunction "GPIO1_14_16") (pintype "passive"))
    )
    (net (code "83") (name "Net-(U$1-GPIO1_15)") (class "Default")
      (node (ref "P8-2") (pin "10") (pinfunction "10_10") (pintype "passive"))
      (node (ref "U$1") (pin "15") (pinfunction "GPIO1_15_15") (pintype "passive"))
    )
    (net (code "84") (name "Net-(U$1-GPIO1_17)") (class "Default")
      (node (ref "P9-2") (pin "18") (pinfunction "18_18") (pintype "passive"))
      (node (ref "U$1") (pin "69") (pinfunction "GPIO1_17_69") (pintype "passive"))
    )
    (net (code "85") (name "Net-(U$1-GPIO1_29)") (class "Default")
      (node (ref "P8-2") (pin "19") (pinfunction "19_19") (pintype "passive"))
      (node (ref "U$1") (pin "26") (pinfunction "GPIO1_29_26") (pintype "passive"))
    )
    (net (code "86") (name "Net-(U$1-GPIO1_30)") (class "Default")
      (node (ref "P8-2") (pin "16") (pinfunction "16_16") (pintype "passive"))
      (node (ref "U$1") (pin "21") (pinfunction "GPIO1_30_21") (pintype "passive"))
    )
    (net (code "87") (name "Net-(U$1-GPIO1_31)") (class "Default")
      (node (ref "P8-2") (pin "13") (pinfunction "13_13") (pintype "passive"))
      (node (ref "U$1") (pin "20") (pinfunction "GPIO1_31_20") (pintype "passive"))
    )
    (net (code "88") (name "Net-(U$1-GPIO2_1)") (class "Default")
      (node (ref "P8-2") (pin "11") (pinfunction "11_11") (pintype "passive"))
      (node (ref "U$1") (pin "18") (pinfunction "GPIO2_1_18") (pintype "passive"))
    )
    (net (code "89") (name "Net-(U$1-GPIO2_6)") (class "Default")
      (node (ref "P8-3") (pin "6") (pinfunction "6_6") (pintype "passive"))
      (node (ref "U$1") (pin "45") (pinfunction "GPIO2_6_45") (pintype "passive"))
    )
    (net (code "90") (name "Net-(U$1-GPIO2_7)") (class "Default")
      (node (ref "P8-3") (pin "5") (pinfunction "5_5") (pintype "passive"))
      (node (ref "U$1") (pin "46") (pinfunction "GPIO2_7_46") (pintype "passive"))
    )
    (net (code "91") (name "Net-(U$1-GPIO2_8)") (class "Default")
      (node (ref "P8-3") (pin "4") (pinfunction "4_4") (pintype "passive"))
      (node (ref "U$1") (pin "43") (pinfunction "GPIO2_8_43") (pintype "passive"))
    )
    (net (code "92") (name "Net-(U$1-GPIO2_9)") (class "Default")
      (node (ref "P8-3") (pin "3") (pinfunction "3_3") (pintype "passive"))
      (node (ref "U$1") (pin "44") (pinfunction "GPIO2_9_44") (pintype "passive"))
    )
    (net (code "93") (name "Net-(U$1-GPIO2_10)") (class "Default")
      (node (ref "P8-3") (pin "2") (pinfunction "2_2") (pintype "passive"))
      (node (ref "U$1") (pin "41") (pinfunction "GPIO2_10_41") (pintype "passive"))
    )
    (net (code "94") (name "Net-(U$1-GPIO2_11)") (class "Default")
      (node (ref "P8-3") (pin "1") (pinfunction "1_1") (pintype "passive"))
      (node (ref "U$1") (pin "42") (pinfunction "GPIO2_11_42") (pintype "passive"))
    )
    (net (code "95") (name "Net-(U$1-GPIO2_12)") (class "Default")
      (node (ref "P8-2") (pin "34") (pinfunction "34_34") (pintype "passive"))
      (node (ref "U$1") (pin "39") (pinfunction "GPIO2_12_39") (pintype "passive"))
    )
    (net (code "96") (name "Net-(U$1-GPIO2_13)") (class "Default")
      (node (ref "P8-2") (pin "33") (pinfunction "33_33") (pintype "passive"))
      (node (ref "U$1") (pin "40") (pinfunction "GPIO2_13_40") (pintype "passive"))
    )
    (net (code "97") (name "Net-(U$1-GPIO2_22)") (class "Default")
      (node (ref "P8-2") (pin "22") (pinfunction "22_22") (pintype "passive"))
      (node (ref "U$1") (pin "27") (pinfunction "GPIO2_22_27") (pintype "passive"))
    )
    (net (code "98") (name "Net-(U$1-GPIO2_23)") (class "Default")
      (node (ref "P8-2") (pin "24") (pinfunction "24_24") (pintype "passive"))
      (node (ref "U$1") (pin "29") (pinfunction "GPIO2_23_29") (pintype "passive"))
    )
    (net (code "99") (name "Net-(U$1-GPIO2_24)") (class "Default")
      (node (ref "P8-2") (pin "21") (pinfunction "21_21") (pintype "passive"))
      (node (ref "U$1") (pin "28") (pinfunction "GPIO2_24_28") (pintype "passive"))
    )
    (net (code "100") (name "Net-(U$1-GPIO2_25)") (class "Default")
      (node (ref "P8-2") (pin "23") (pinfunction "23_23") (pintype "passive"))
      (node (ref "U$1") (pin "30") (pinfunction "GPIO2_25_30") (pintype "passive"))
    )
    (net (code "101") (name "Net-(U$1-GPIO3_19)") (class "Default")
      (node (ref "P9-2") (pin "22") (pinfunction "22_22") (pintype "passive"))
      (node (ref "U$1") (pin "73") (pinfunction "GPIO3_19_73") (pintype "passive"))
    )
    (net (code "102") (name "Net-(U$1-GPIO3_21)") (class "Default")
      (node (ref "P9-2") (pin "20") (pinfunction "20_20") (pintype "passive"))
      (node (ref "U$1") (pin "71") (pinfunction "GPIO3_21_71") (pintype "passive"))
    )
    (net (code "103") (name "Net-(U$1-I2C1_SCL)") (class "Default")
      (node (ref "P9-2") (pin "12") (pinfunction "12_12") (pintype "passive"))
      (node (ref "U$1") (pin "63") (pinfunction "I2C1_SCL_63") (pintype "passive"))
    )
    (net (code "104") (name "Net-(U$1-I2C1_SDA)") (class "Default")
      (node (ref "P9-2") (pin "11") (pinfunction "11_11") (pintype "passive"))
      (node (ref "U$1") (pin "64") (pinfunction "I2C1_SDA_64") (pintype "passive"))
    )
    (net (code "105") (name "Net-(U$1-PWR_BUT)") (class "Default")
      (node (ref "P9-2") (pin "4") (pinfunction "4_4") (pintype "passive"))
      (node (ref "U$1") (pin "55") (pinfunction "PWR_BUT_55") (pintype "passive"))
    )
    (net (code "106") (name "Net-(U$1-SPI1_CS0)") (class "Default")
      (node (ref "P9-2") (pin "21") (pinfunction "21_21") (pintype "passive"))
      (node (ref "U$1") (pin "74") (pinfunction "SPI1_CS0_74") (pintype "passive"))
    )
    (net (code "107") (name "Net-(U$1-SPI1_DI)") (class "Default")
      (node (ref "P9-2") (pin "23") (pinfunction "23_23") (pintype "passive"))
      (node (ref "U$1") (pin "76") (pinfunction "SPI1_DI_76") (pintype "passive"))
    )
    (net (code "108") (name "Net-(U$1-SPI1_DO)") (class "Default")
      (node (ref "P9-2") (pin "24") (pinfunction "24_24") (pintype "passive"))
      (node (ref "U$1") (pin "75") (pinfunction "SPI1_DO_75") (pintype "passive"))
    )
    (net (code "109") (name "Net-(U$1-SPI1_SCLK)") (class "Default")
      (node (ref "P9-2") (pin "26") (pinfunction "26_26") (pintype "passive"))
      (node (ref "U$1") (pin "77") (pinfunction "SPI1_SCLK_77") (pintype "passive"))
    )
    (net (code "110") (name "Net-(U$1-SYS_RESETN)") (class "Default")
      (node (ref "P9-2") (pin "3") (pinfunction "3_3") (pintype "passive"))
      (node (ref "U$1") (pin "56") (pinfunction "SYS_RESETN_56") (pintype "passive"))
    )
    (net (code "111") (name "Net-(U$1-TIMER4)") (class "Default")
      (node (ref "P8-2") (pin "2") (pinfunction "2_2") (pintype "passive"))
      (node (ref "U$1") (pin "7") (pinfunction "TIMER4_7") (pintype "passive"))
    )
    (net (code "112") (name "Net-(U$1-TIMER5)") (class "Default")
      (node (ref "P8-2") (pin "4") (pinfunction "4_4") (pintype "passive"))
      (node (ref "U$1") (pin "9") (pinfunction "TIMER5_9") (pintype "passive"))
    )
    (net (code "113") (name "Net-(U$1-TIMER6)") (class "Default")
      (node (ref "P8-2") (pin "3") (pinfunction "3_3") (pintype "passive"))
      (node (ref "U$1") (pin "10") (pinfunction "TIMER6_10") (pintype "passive"))
    )
    (net (code "114") (name "Net-(U$1-TIMER7)") (class "Default")
      (node (ref "P8-2") (pin "1") (pinfunction "1_1") (pintype "passive"))
      (node (ref "U$1") (pin "8") (pinfunction "TIMER7_8") (pintype "passive"))
    )
    (net (code "115") (name "Net-(U$1-UART1_RXD)") (class "Default")
      (node (ref "P9-2") (pin "19") (pinfunction "19_19") (pintype "passive"))
      (node (ref "U$1") (pin "72") (pinfunction "UART1_RXD_72") (pintype "passive"))
    )
    (net (code "116") (name "Net-(U$1-UART1_TXD)") (class "Default")
      (node (ref "P9-2") (pin "17") (pinfunction "17_17") (pintype "passive"))
      (node (ref "U$1") (pin "70") (pinfunction "UART1_TXD_70") (pintype "passive"))
    )
    (net (code "117") (name "Net-(U$1-UART2_RXD)") (class "Default")
      (node (ref "P9-2") (pin "15") (pinfunction "15_15") (pintype "passive"))
      (node (ref "U$1") (pin "68") (pinfunction "UART2_RXD_68") (pintype "passive"))
    )
    (net (code "118") (name "Net-(U$1-UART2_TXD)") (class "Default")
      (node (ref "P9-2") (pin "16") (pinfunction "16_16") (pintype "passive"))
      (node (ref "U$1") (pin "67") (pinfunction "UART2_TXD_67") (pintype "passive"))
    )
    (net (code "119") (name "Net-(U$1-UART3_CTSN)") (class "Default")
      (node (ref "P8-2") (pin "29") (pinfunction "29_29") (pintype "passive"))
      (node (ref "U$1") (pin "36") (pinfunction "UART3_CTSN_36") (pintype "passive"))
    )
    (net (code "120") (name "Net-(U$1-UART3_RTSN)") (class "Default")
      (node (ref "P8-2") (pin "27") (pinfunction "27_27") (pintype "passive"))
      (node (ref "U$1") (pin "34") (pinfunction "UART3_RTSN_34") (pintype "passive"))
    )
    (net (code "121") (name "Net-(U$1-UART4_CTSN)") (class "Default")
      (node (ref "P8-2") (pin "30") (pinfunction "30_30") (pintype "passive"))
      (node (ref "U$1") (pin "35") (pinfunction "UART4_CTSN_35") (pintype "passive"))
    )
    (net (code "122") (name "Net-(U$1-UART4_RTSN)") (class "Default")
      (node (ref "P8-2") (pin "28") (pinfunction "28_28") (pintype "passive"))
      (node (ref "U$1") (pin "33") (pinfunction "UART4_RTSN_33") (pintype "passive"))
    )
    (net (code "123") (name "Net-(U$1-UART5_CTSN)") (class "Default")
      (node (ref "P8-2") (pin "26") (pinfunction "26_26") (pintype "passive"))
      (node (ref "U$1") (pin "31") (pinfunction "UART5_CTSN_31") (pintype "passive"))
    )
    (net (code "124") (name "Net-(U$1-UART5_RTSN)") (class "Default")
      (node (ref "P8-2") (pin "25") (pinfunction "25_25") (pintype "passive"))
      (node (ref "U$1") (pin "32") (pinfunction "UART5_RTSN_32") (pintype "passive"))
    )
    (net (code "125") (name "Net-(U$1-UART5_RXD)") (class "Default")
      (node (ref "P8-2") (pin "31") (pinfunction "31_31") (pintype "passive"))
      (node (ref "U$1") (pin "38") (pinfunction "UART5_RXD_38") (pintype "passive"))
    )
    (net (code "126") (name "Net-(U$1-UART5_TXD)") (class "Default")
      (node (ref "P8-2") (pin "32") (pinfunction "32_32") (pintype "passive"))
      (node (ref "U$1") (pin "37") (pinfunction "UART5_TXD_37") (pintype "passive"))
    )
    (net (code "127") (name "Net-(U$1-VDD_ADC)") (class "Default")
      (node (ref "P9-2") (pin "25") (pinfunction "25_25") (pintype "passive"))
      (node (ref "U$1") (pin "78") (pinfunction "VDD_ADC_78") (pintype "passive"))
    )
    (net (code "128") (name "VCC") (class "Default")
      (node (ref "74HC595") (pin "10") (pinfunction "SCL_10") (pintype "input"))
      (node (ref "74HC595") (pin "16") (pinfunction "VCC_16") (pintype "power_in"))
      (node (ref "C3") (pin "1") (pinfunction "1_1") (pintype "passive"))
      (node (ref "EXTOUT1") (pin "8") (pinfunction "8_8") (pintype "passive"))
      (node (ref "P9-1") (pin "3") (pinfunction "3_3") (pintype "passive"))
      (node (ref "P9-1") (pin "4") (pinfunction "4_4") (pintype "passive"))
      (node (ref "ROE") (pin "2") (pinfunction "2_2") (pintype "passive"))
      (node (ref "RSU") (pin "2") (pinfunction "2_2") (pintype "passive"))
      (node (ref "U$1") (pin "49") (pinfunction "VDD_3V3EXP_49") (pintype "power_in"))
      (node (ref "U$1") (pin "50") (pinfunction "VDD_3V3EXP_50") (pintype "power_in"))
    )
    (net (code "129") (name "unconnected-(DS1307-SQW{slash}OUT-Pad7)") (class "Default")
      (node (ref "DS1307") (pin "7") (pinfunction "SQW/OUT_7") (pintype "bidirectional"))
    )
    (net (code "130") (name "unconnected-(T1-M2-Pad2)") (class "Default")
      (node (ref "T1") (pin "2") (pinfunction "M2_2") (pintype "bidirectional"))
    )
    (net (code "131") (name "unconnected-(T2-M2-Pad2)") (class "Default")
      (node (ref "T2") (pin "2") (pinfunction "M2_2") (pintype "bidirectional"))
    )
    (net (code "132") (name "unconnected-(T3-M2-Pad2)") (class "Default")
      (node (ref "T3") (pin "2") (pinfunction "M2_2") (pintype "bidirectional"))
    )
    (net (code "133") (name "unconnected-(T4-M2-Pad2)") (class "Default")
      (node (ref "T4") (pin "2") (pinfunction "M2_2") (pintype "bidirectional"))
    )
    (net (code "134") (name "unconnected-(T5-M2-Pad2)") (class "Default")
      (node (ref "T5") (pin "2") (pinfunction "M2_2") (pintype "bidirectional"))
    )
    (net (code "135") (name "unconnected-(T6-M2-Pad2)") (class "Default")
      (node (ref "T6") (pin "2") (pinfunction "M2_2") (pintype "bidirectional"))
    )
    (net (code "136") (name "unconnected-(T7-M2-Pad2)") (class "Default")
      (node (ref "T7") (pin "2") (pinfunction "M2_2") (pintype "bidirectional"))
    )
    (net (code "137") (name "unconnected-(T8-M2-Pad2)") (class "Default")
      (node (ref "T8") (pin "2") (pinfunction "M2_2") (pintype "bidirectional"))
    )
  )
)
